# MINIRACER-POWER.net
KiCad netlist of a schematic drawn in Altium Designer
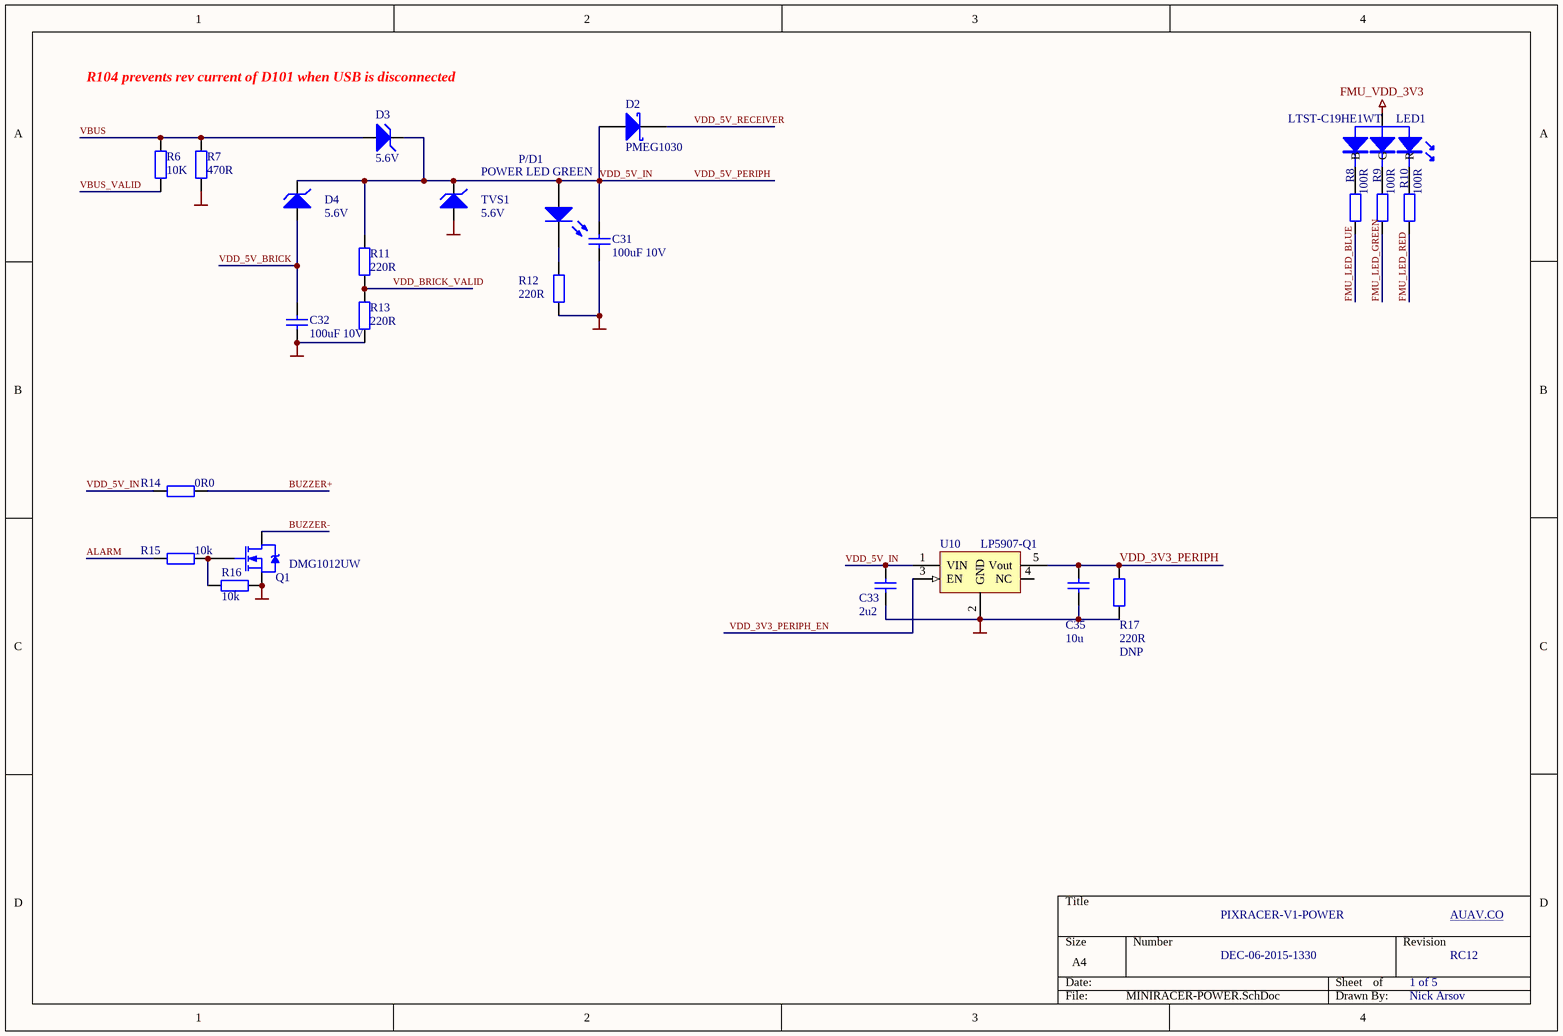
[diagram p0: MINIRACER-POWER.SchDoc]

(export (version "E")
  (design (tool "Eeschema 10.0.6"))
  (components
    (comp (ref "C31")
      (value "100uF 10V")
      (footprint "0805A")
      (description "Capacitor")
      (fields (field (name "PUBLISHER") "Altium Limited"))
      (libsource (lib "Miscellaneous Devices") (part "Cap"))
    )
    (comp (ref "C32")
      (value "100uF 10V")
      (footprint "0805A")
      (description "Capacitor")
      (fields (field (name "PUBLISHER") "Altium Limited"))
      (libsource (lib "Miscellaneous Devices") (part "Cap"))
    )
    (comp (ref "C33")
      (value "2u2")
      (footprint "0603A")
      (description "Capacitor")
      (fields (field (name "PUBLISHER") "Altium Limited"))
      (libsource (lib "Miscellaneous Devices") (part "Cap"))
    )
    (comp (ref "C35")
      (value "10u")
      (footprint "0603A")
      (description "Capacitor")
      (fields (field (name "PUBLISHER") "Altium Limited"))
      (libsource (lib "Miscellaneous Devices") (part "Cap"))
    )
    (comp (ref "D2")
      (value "PMEG1030")
      (footprint "sod323f")
      (description "Schottky Diode")
      (fields (field (name "PUBLISHER") "Altium Limited"))
      (libsource (lib "Miscellaneous Devices") (part "D Schottky"))
    )
    (comp (ref "D3")
      (value "5.6V")
      (footprint "SOD123F")
      (description "Zener Diode")
      (fields (field (name "PUBLISHER") "Altium Limited"))
      (libsource (lib "Miscellaneous Devices") (part "D Zener"))
    )
    (comp (ref "D4")
      (value "5.6V")
      (footprint "SOD123F")
      (description "Zener Diode")
      (fields (field (name "PUBLISHER") "Altium Limited"))
      (libsource (lib "Miscellaneous Devices") (part "D Zener"))
    )
    (comp (ref "LED1")
      (value "LTST-C19HE1WT")
      (footprint "LTST-C19HE1WT")
      (libsource (lib "My_Altium") (part "RGB_LED_5MM"))
    )
    (comp (ref "P/D1")
      (value "POWER LED GREEN")
      (footprint "0603A")
      (description "Typical INFRARED GaAs LED")
      (fields (field (name "PUBLISHER") "Altium Limited"))
      (libsource (lib "Miscellaneous Devices") (part "LED0"))
    )
    (comp (ref "Q1")
      (value "DMG1012UW")
      (footprint "2N7002-SOT323")
      (description "N-Channel Power MOSFET")
      (fields (field (name "PUBLISHER") "Altium Limited"))
      (libsource (lib "Miscellaneous Devices") (part "NMOS-2"))
    )
    (comp (ref "R6")
      (value "10K")
      (footprint "0603A")
      (description "Resistor")
      (fields (field (name "PUBLISHER") "Altium Limited"))
      (libsource (lib "") (part "Res2_1"))
    )
    (comp (ref "R7")
      (value "470R")
      (footprint "0603A")
      (description "Resistor")
      (fields (field (name "PUBLISHER") "Altium Limited"))
      (libsource (lib "") (part "Res2_1"))
    )
    (comp (ref "R8")
      (value "100R")
      (footprint "0402A")
      (description "Resistor")
      (fields (field (name "PUBLISHER") "Altium Limited"))
      (libsource (lib "") (part "Res2_1"))
    )
    (comp (ref "R9")
      (value "100R")
      (footprint "0402A")
      (description "Resistor")
      (fields (field (name "PUBLISHER") "Altium Limited"))
      (libsource (lib "") (part "Res2_1"))
    )
    (comp (ref "R10")
      (value "100R")
      (footprint "0402A")
      (description "Resistor")
      (fields (field (name "PUBLISHER") "Altium Limited"))
      (libsource (lib "") (part "Res2_1"))
    )
    (comp (ref "R11")
      (value "220R")
      (footprint "0603A")
      (description "Resistor")
      (fields (field (name "PUBLISHER") "Altium Limited"))
      (libsource (lib "Miscellaneous Devices") (part "Res2"))
    )
    (comp (ref "R12")
      (value "220R")
      (footprint "0603A")
      (description "Resistor")
      (fields (field (name "PUBLISHER") "Altium Limited"))
      (libsource (lib "") (part "Res2_1"))
    )
    (comp (ref "R13")
      (value "220R")
      (footprint "0603A")
      (description "Resistor")
      (fields (field (name "PUBLISHER") "Altium Limited"))
      (libsource (lib "Miscellaneous Devices") (part "Res2"))
    )
    (comp (ref "R14")
      (value "0R0")
      (footprint "0402A")
      (description "Resistor")
      (fields (field (name "PUBLISHER") "Altium Limited"))
      (libsource (lib "") (part "Res2_3"))
    )
    (comp (ref "R15")
      (value "10k")
      (footprint "0402A")
      (description "Resistor")
      (fields (field (name "PUBLISHER") "Altium Limited"))
      (libsource (lib "") (part "Res2_3"))
    )
    (comp (ref "R16")
      (value "10k")
      (footprint "0402A")
      (description "Resistor")
      (fields (field (name "PUBLISHER") "Altium Limited"))
      (libsource (lib "") (part "Res2_2"))
    )
    (comp (ref "R17")
      (value "220R")
      (footprint "0402A")
      (description "Resistor")
      (fields (field (name "REM") "DNP") (field (name "PUBLISHER") "Altium Limited"))
      (libsource (lib "") (part "Res2_1"))
    )
    (comp (ref "TVS1")
      (value "5.6V")
      (footprint "SOD123F")
      (description "Zener Diode")
      (fields (field (name "PUBLISHER") "Altium Limited"))
      (libsource (lib "Miscellaneous Devices") (part "D Zener"))
    )
    (comp (ref "U10")
      (value "LP5907-Q1")
      (footprint "SOT23-5")
      (libsource (lib "My_Altium") (part "LP5907-Q1"))
    )
  )
  (nets
    (net (code "1") (name "/ALARM") (class "Default")
      (node (ref "R15") (pin "2") (pinfunction "2_2") (pintype "passive"))
    )
    (net (code "2") (name "/BUZZER+") (class "Default")
      (node (ref "R14") (pin "1") (pinfunction "1_1") (pintype "passive"))
    )
    (net (code "3") (name "/BUZZER-") (class "Default")
      (node (ref "Q1") (pin "1") (pinfunction "D_1") (pintype "passive"))
    )
    (net (code "4") (name "/FMU_LED_BLUE") (class "Default")
      (node (ref "R8") (pin "1") (pinfunction "1_1") (pintype "passive"))
    )
    (net (code "5") (name "/FMU_LED_GREEN") (class "Default")
      (node (ref "R9") (pin "1") (pinfunction "1_1") (pintype "passive"))
    )
    (net (code "6") (name "/FMU_LED_RED") (class "Default")
      (node (ref "R10") (pin "1") (pinfunction "1_1") (pintype "passive"))
    )
    (net (code "7") (name "/VBUS") (class "Default")
      (node (ref "D3") (pin "1") (pinfunction "A_1") (pintype "passive"))
      (node (ref "R6") (pin "2") (pinfunction "2_2") (pintype "passive"))
      (node (ref "R7") (pin "2") (pinfunction "2_2") (pintype "passive"))
    )
    (net (code "8") (name "/VBUS_VALID") (class "Default")
      (node (ref "R6") (pin "1") (pinfunction "1_1") (pintype "passive"))
    )
    (net (code "9") (name "/VDD_3V3_PERIPH") (class "Default")
      (node (ref "C35") (pin "2") (pinfunction "2_2") (pintype "passive"))
      (node (ref "R17") (pin "2") (pinfunction "2_2") (pintype "passive"))
      (node (ref "U10") (pin "5") (pinfunction "Vout_5") (pintype "power_in"))
    )
    (net (code "10") (name "/VDD_3V3_PERIPH_EN") (class "Default")
      (node (ref "U10") (pin "3") (pinfunction "EN_3") (pintype "input"))
    )
    (net (code "11") (name "/VDD_5V_BRICK") (class "Default")
      (node (ref "C32") (pin "2") (pinfunction "2_2") (pintype "passive"))
      (node (ref "D4") (pin "1") (pinfunction "A_1") (pintype "passive"))
    )
    (net (code "12") (name "/VDD_5V_IN") (class "Default")
      (node (ref "C31") (pin "2") (pinfunction "2_2") (pintype "passive"))
      (node (ref "C33") (pin "2") (pinfunction "2_2") (pintype "passive"))
      (node (ref "D2") (pin "1") (pinfunction "A_1") (pintype "passive"))
      (node (ref "D3") (pin "2") (pinfunction "K_2") (pintype "passive"))
      (node (ref "D4") (pin "2") (pinfunction "K_2") (pintype "passive"))
      (node (ref "P/D1") (pin "1") (pinfunction "A_1") (pintype "passive"))
      (node (ref "R11") (pin "1") (pinfunction "1_1") (pintype "passive"))
      (node (ref "R14") (pin "2") (pinfunction "2_2") (pintype "passive"))
      (node (ref "TVS1") (pin "2") (pinfunction "K_2") (pintype "passive"))
      (node (ref "U10") (pin "1") (pinfunction "VIN_1") (pintype "power_in"))
    )
    (net (code "13") (name "/VDD_5V_RECEIVER") (class "Default")
      (node (ref "D2") (pin "2") (pinfunction "K_2") (pintype "passive"))
    )
    (net (code "14") (name "/VDD_BRICK_VALID") (class "Default")
      (node (ref "R11") (pin "2") (pinfunction "2_2") (pintype "passive"))
      (node (ref "R13") (pin "1") (pinfunction "1_1") (pintype "passive"))
    )
    (net (code "15") (name "FMU_VDD_3V3") (class "Default")
      (node (ref "LED1") (pin "4") (pinfunction "A_4") (pintype "passive"))
    )
    (net (code "16") (name "GND") (class "Default")
      (node (ref "C31") (pin "1") (pinfunction "1_1") (pintype "passive"))
      (node (ref "C32") (pin "1") (pinfunction "1_1") (pintype "passive"))
      (node (ref "C33") (pin "1") (pinfunction "1_1") (pintype "passive"))
      (node (ref "C35") (pin "1") (pinfunction "1_1") (pintype "passive"))
      (node (ref "Q1") (pin "2") (pinfunction "S_2") (pintype "passive"))
      (node (ref "R12") (pin "1") (pinfunction "1_1") (pintype "passive"))
      (node (ref "R13") (pin "2") (pinfunction "2_2") (pintype "passive"))
      (node (ref "R16") (pin "2") (pinfunction "2_2") (pintype "passive"))
      (node (ref "R17") (pin "1") (pinfunction "1_1") (pintype "passive"))
      (node (ref "R7") (pin "1") (pinfunction "1_1") (pintype "passive"))
      (node (ref "TVS1") (pin "1") (pinfunction "A_1") (pintype "passive"))
      (node (ref "U10") (pin "2") (pinfunction "GND_2") (pintype "power_in"))
    )
    (net (code "17") (name "Net-(LED1-B)") (class "Default")
      (node (ref "LED1") (pin "3") (pinfunction "B_3") (pintype "passive"))
      (node (ref "R8") (pin "2") (pinfunction "2_2") (pintype "passive"))
    )
    (net (code "18") (name "Net-(LED1-G)") (class "Default")
      (node (ref "LED1") (pin "2") (pinfunction "G_2") (pintype "passive"))
      (node (ref "R9") (pin "2") (pinfunction "2_2") (pintype "passive"))
    )
    (net (code "19") (name "Net-(LED1-R)") (class "Default")
      (node (ref "LED1") (pin "1") (pinfunction "R_1") (pintype "passive"))
      (node (ref "R10") (pin "2") (pinfunction "2_2") (pintype "passive"))
    )
    (net (code "20") (name "Net-(P/D1-K)") (class "Default")
      (node (ref "P/D1") (pin "2") (pinfunction "K_2") (pintype "passive"))
      (node (ref "R12") (pin "2") (pinfunction "2_2") (pintype "passive"))
    )
    (net (code "21") (name "Net-(Q1-G)") (class "Default")
      (node (ref "Q1") (pin "3") (pinfunction "G_3") (pintype "passive"))
      (node (ref "R15") (pin "1") (pinfunction "1_1") (pintype "passive"))
      (node (ref "R16") (pin "1") (pinfunction "1_1") (pintype "passive"))
    )
    (net (code "22") (name "unconnected-(U10-NC-Pad4)") (class "Default")
      (node (ref "U10") (pin "4") (pinfunction "NC_4") (pintype "passive"))
    )
  )
)
